# P02_MCU_USB.net
KiCad netlist of a schematic drawn in EasyEDA
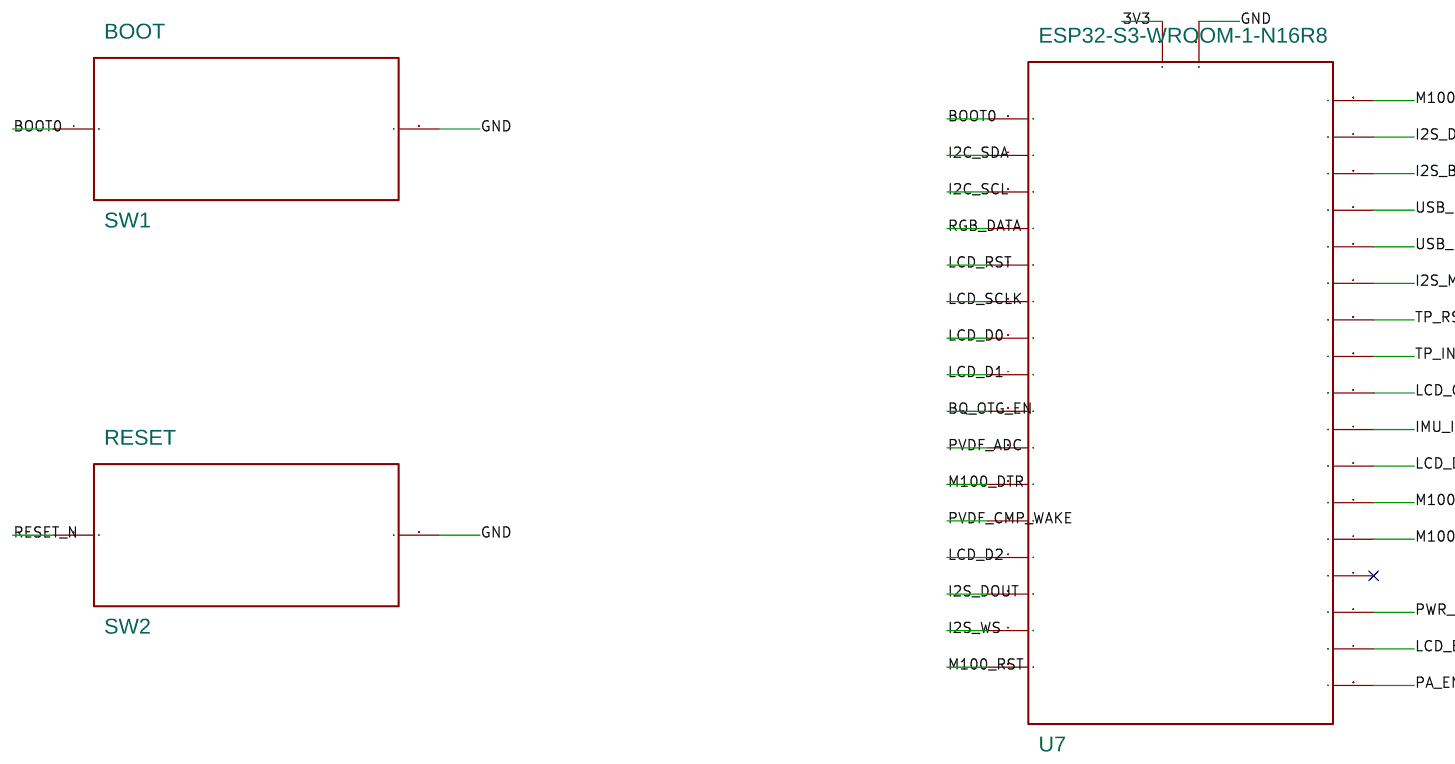
[diagram p0: schematic sheet]

(export (version "E")
  (design (tool "Eeschema 10.0.6"))
  (components
    (comp (ref "SW1") (value "BOOT") (libsource (lib "") (part "Switch")))
    (comp (ref "SW2") (value "RESET") (libsource (lib "") (part "Switch")))
    (comp (ref "U7") (value "ESP32-S3-WROOM-1-N16R8") (libsource (lib "") (part "ESP32_S3_WROOM")))
  )
  (nets
    (net (code "1") (name "/3V3") (class "Default")
      (node (ref "U7") (pin "49") (pinfunction "1_49") (pintype "unspecified"))
    )
    (net (code "2") (name "/BOOT0") (class "Default")
      (node (ref "SW1") (pin "1") (pinfunction "1_1") (pintype "unspecified"))
      (node (ref "U7") (pin "0") (pinfunction "1_0") (pintype "unspecified"))
    )
    (net (code "3") (name "/BQ_OTG_EN") (class "Default")
      (node (ref "U7") (pin "8") (pinfunction "1_8") (pintype "unspecified"))
    )
    (net (code "4") (name "/GND") (class "Default")
      (node (ref "SW1") (pin "2") (pinfunction "1_2") (pintype "unspecified"))
      (node (ref "SW2") (pin "2") (pinfunction "1_2") (pintype "unspecified"))
      (node (ref "U7") (pin "50") (pinfunction "1_50") (pintype "unspecified"))
    )
    (net (code "5") (name "/I2C_SCL") (class "Default")
      (node (ref "U7") (pin "2") (pinfunction "1_2") (pintype "unspecified"))
    )
    (net (code "6") (name "/I2C_SDA") (class "Default")
      (node (ref "U7") (pin "1") (pinfunction "1_1") (pintype "unspecified"))
    )
    (net (code "7") (name "/I2S_BCLK") (class "Default")
      (node (ref "U7") (pin "18") (pinfunction "1_18") (pintype "unspecified"))
    )
    (net (code "8") (name "/I2S_DIN") (class "Default")
      (node (ref "U7") (pin "17") (pinfunction "1_17") (pintype "unspecified"))
    )
    (net (code "9") (name "/I2S_DOUT") (class "Default")
      (node (ref "U7") (pin "13") (pinfunction "1_13") (pintype "unspecified"))
    )
    (net (code "10") (name "/I2S_MCLK") (class "Default")
      (node (ref "U7") (pin "21") (pinfunction "1_21") (pintype "unspecified"))
    )
    (net (code "11") (name "/I2S_WS") (class "Default")
      (node (ref "U7") (pin "14") (pinfunction "1_14") (pintype "unspecified"))
    )
    (net (code "12") (name "/IMU_INT1") (class "Default")
      (node (ref "U7") (pin "41") (pinfunction "1_41") (pintype "unspecified"))
    )
    (net (code "13") (name "/LCD_CS") (class "Default")
      (node (ref "U7") (pin "40") (pinfunction "1_40") (pintype "unspecified"))
    )
    (net (code "14") (name "/LCD_D0") (class "Default")
      (node (ref "U7") (pin "6") (pinfunction "1_6") (pintype "unspecified"))
    )
    (net (code "15") (name "/LCD_D1") (class "Default")
      (node (ref "U7") (pin "7") (pinfunction "1_7") (pintype "unspecified"))
    )
    (net (code "16") (name "/LCD_D2") (class "Default")
      (node (ref "U7") (pin "12") (pinfunction "1_12") (pintype "unspecified"))
    )
    (net (code "17") (name "/LCD_D3") (class "Default")
      (node (ref "U7") (pin "42") (pinfunction "1_42") (pintype "unspecified"))
    )
    (net (code "18") (name "/LCD_EN") (class "Default")
      (node (ref "U7") (pin "47") (pinfunction "1_47") (pintype "unspecified"))
    )
    (net (code "19") (name "/LCD_RST") (class "Default")
      (node (ref "U7") (pin "4") (pinfunction "1_4") (pintype "unspecified"))
    )
    (net (code "20") (name "/LCD_SCLK") (class "Default")
      (node (ref "U7") (pin "5") (pinfunction "1_5") (pintype "unspecified"))
    )
    (net (code "21") (name "/M100_DTR") (class "Default")
      (node (ref "U7") (pin "10") (pinfunction "1_10") (pintype "unspecified"))
    )
    (net (code "22") (name "/M100_NET_STATUS_COMPAT") (class "Default")
      (node (ref "U7") (pin "16") (pinfunction "1_16") (pintype "unspecified"))
    )
    (net (code "23") (name "/M100_RST") (class "Default")
      (node (ref "U7") (pin "15") (pinfunction "1_15") (pintype "unspecified"))
    )
    (net (code "24") (name "/M100_RXD") (class "Default")
      (node (ref "U7") (pin "44") (pinfunction "1_44") (pintype "unspecified"))
    )
    (net (code "25") (name "/M100_TXD") (class "Default")
      (node (ref "U7") (pin "43") (pinfunction "1_43") (pintype "unspecified"))
    )
    (net (code "26") (name "/PA_EN") (class "Default")
      (node (ref "U7") (pin "48") (pinfunction "1_48") (pintype "unspecified"))
    )
    (net (code "27") (name "/PVDF_ADC") (class "Default")
      (node (ref "U7") (pin "9") (pinfunction "1_9") (pintype "unspecified"))
    )
    (net (code "28") (name "/PVDF_CMP_WAKE") (class "Default")
      (node (ref "U7") (pin "11") (pinfunction "1_11") (pintype "unspecified"))
    )
    (net (code "29") (name "/PWR_STATE") (class "Default")
      (node (ref "U7") (pin "46") (pinfunction "1_46") (pintype "unspecified"))
    )
    (net (code "30") (name "/RESET_N") (class "Default")
      (node (ref "SW2") (pin "1") (pinfunction "1_1") (pintype "unspecified"))
    )
    (net (code "31") (name "/RGB_DATA") (class "Default")
      (node (ref "U7") (pin "3") (pinfunction "1_3") (pintype "unspecified"))
    )
    (net (code "32") (name "/TP_INT") (class "Default")
      (node (ref "U7") (pin "39") (pinfunction "1_39") (pintype "unspecified"))
    )
    (net (code "33") (name "/TP_RST") (class "Default")
      (node (ref "U7") (pin "38") (pinfunction "1_38") (pintype "unspecified"))
    )
    (net (code "34") (name "/USB_D+") (class "Default")
      (node (ref "U7") (pin "20") (pinfunction "1_20") (pintype "unspecified"))
    )
    (net (code "35") (name "/USB_D-") (class "Default")
      (node (ref "U7") (pin "19") (pinfunction "1_19") (pintype "unspecified"))
    )
    (net (code "36") (name "unconnected-(U7-1-Pad45)") (class "Default")
      (node (ref "U7") (pin "45") (pinfunction "1_45") (pintype "unspecified+no_connect"))
    )
  )
)
